# FPGA.net
KiCad netlist of a schematic drawn in Altium Designer
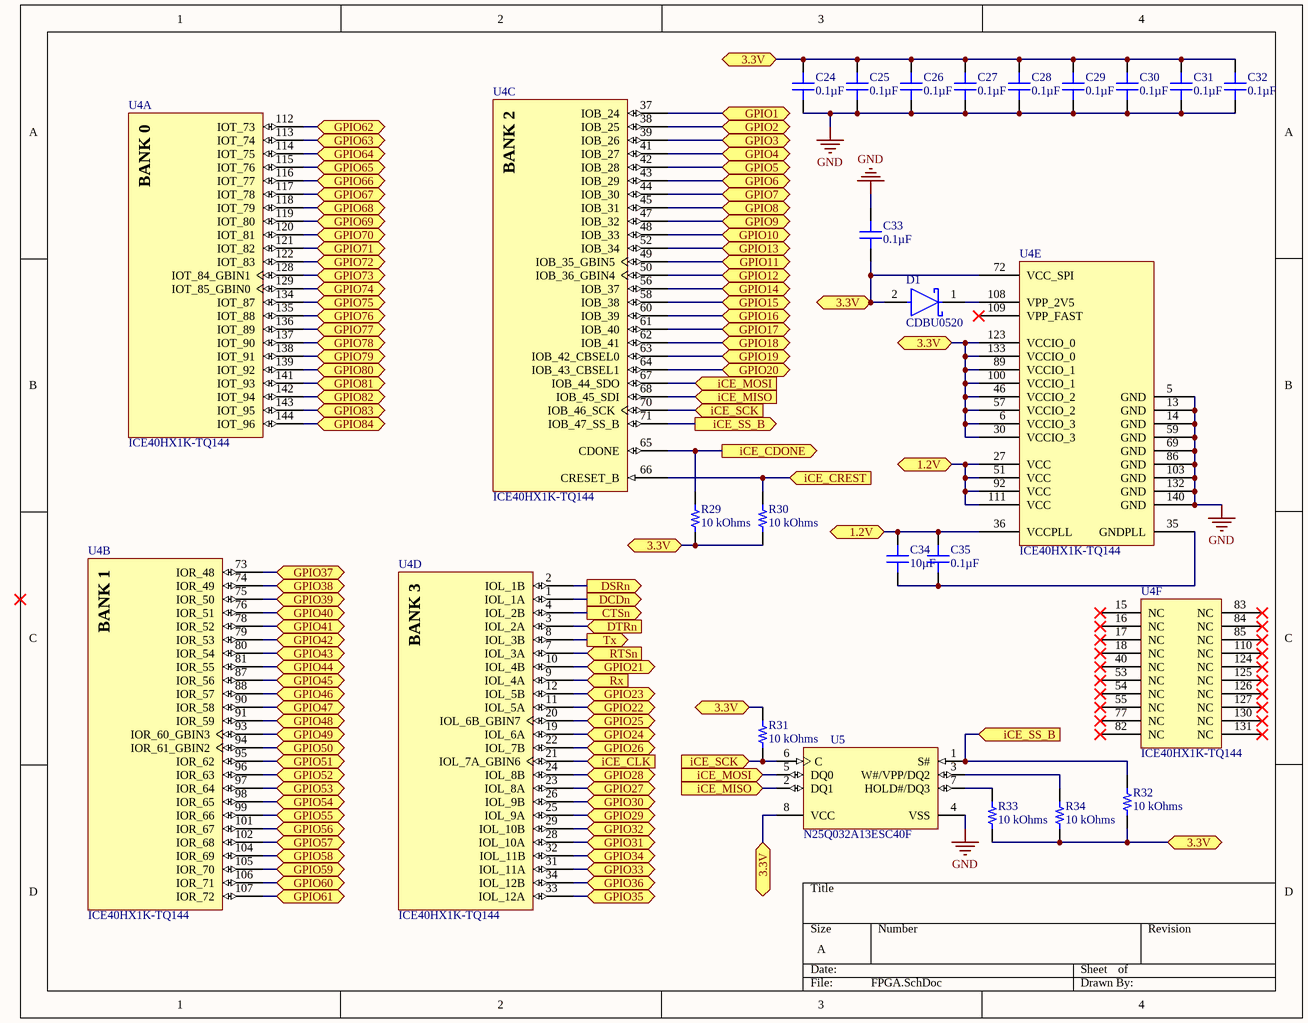
[diagram p0: FPGA.SchDoc]

(export (version "E")
  (design (tool "Eeschema 10.0.6"))
  (components
    (comp (ref "C24")
      (value "0.1µF")
      (footprint "CAP 0805_2012")
      (description "CAP CER 0.1UF 50V X7R 0805")
      (fields
        (field (name "PART NUMBER") "CL21B104KBCNNNC")
        (field (name "MANUFACTURER") "Samsung Electro-Mechanics")
      )
      (libsource (lib "Celestial Altium Library - altium_library") (part "Capacitor"))
    )
    (comp (ref "C25")
      (value "0.1µF")
      (footprint "CAP 0805_2012")
      (description "CAP CER 0.1UF 50V X7R 0805")
      (fields
        (field (name "PART NUMBER") "CL21B104KBCNNNC")
        (field (name "MANUFACTURER") "Samsung Electro-Mechanics")
      )
      (libsource (lib "Celestial Altium Library - altium_library") (part "Capacitor"))
    )
    (comp (ref "C26")
      (value "0.1µF")
      (footprint "CAP 0805_2012")
      (description "CAP CER 0.1UF 50V X7R 0805")
      (fields
        (field (name "PART NUMBER") "CL21B104KBCNNNC")
        (field (name "MANUFACTURER") "Samsung Electro-Mechanics")
      )
      (libsource (lib "Celestial Altium Library - altium_library") (part "Capacitor"))
    )
    (comp (ref "C27")
      (value "0.1µF")
      (footprint "CAP 0805_2012")
      (description "CAP CER 0.1UF 50V X7R 0805")
      (fields
        (field (name "PART NUMBER") "CL21B104KBCNNNC")
        (field (name "MANUFACTURER") "Samsung Electro-Mechanics")
      )
      (libsource (lib "Celestial Altium Library - altium_library") (part "Capacitor"))
    )
    (comp (ref "C28")
      (value "0.1µF")
      (footprint "CAP 0805_2012")
      (description "CAP CER 0.1UF 50V X7R 0805")
      (fields
        (field (name "PART NUMBER") "CL21B104KBCNNNC")
        (field (name "MANUFACTURER") "Samsung Electro-Mechanics")
      )
      (libsource (lib "Celestial Altium Library - altium_library") (part "Capacitor"))
    )
    (comp (ref "C29")
      (value "0.1µF")
      (footprint "CAP 0805_2012")
      (description "CAP CER 0.1UF 50V X7R 0805")
      (fields
        (field (name "PART NUMBER") "CL21B104KBCNNNC")
        (field (name "MANUFACTURER") "Samsung Electro-Mechanics")
      )
      (libsource (lib "Celestial Altium Library - altium_library") (part "Capacitor"))
    )
    (comp (ref "C30")
      (value "0.1µF")
      (footprint "CAP 0805_2012")
      (description "CAP CER 0.1UF 50V X7R 0805")
      (fields
        (field (name "PART NUMBER") "CL21B104KBCNNNC")
        (field (name "MANUFACTURER") "Samsung Electro-Mechanics")
      )
      (libsource (lib "Celestial Altium Library - altium_library") (part "Capacitor"))
    )
    (comp (ref "C31")
      (value "0.1µF")
      (footprint "CAP 0805_2012")
      (description "CAP CER 0.1UF 50V X7R 0805")
      (fields
        (field (name "PART NUMBER") "CL21B104KBCNNNC")
        (field (name "MANUFACTURER") "Samsung Electro-Mechanics")
      )
      (libsource (lib "Celestial Altium Library - altium_library") (part "Capacitor"))
    )
    (comp (ref "C32")
      (value "0.1µF")
      (footprint "CAP 0805_2012")
      (description "CAP CER 0.1UF 50V X7R 0805")
      (fields
        (field (name "PART NUMBER") "CL21B104KBCNNNC")
        (field (name "MANUFACTURER") "Samsung Electro-Mechanics")
      )
      (libsource (lib "Celestial Altium Library - altium_library") (part "Capacitor"))
    )
    (comp (ref "C33")
      (value "0.1µF")
      (footprint "CAP 0805_2012")
      (description "CAP CER 0.1UF 50V X7R 0805")
      (fields
        (field (name "PART NUMBER") "CL21B104KBCNNNC")
        (field (name "MANUFACTURER") "Samsung Electro-Mechanics")
      )
      (libsource (lib "Celestial Altium Library - altium_library") (part "Capacitor"))
    )
    (comp (ref "C34")
      (value "10µF")
      (footprint "CAP 0805_2012")
      (description "CAP CER 10UF 16V X5R 0805")
      (fields
        (field (name "PART NUMBER") "CL21A106KOQNNNG")
        (field (name "MANUFACTURER") "Samsung Electro-Mechanics")
      )
      (libsource (lib "Celestial Altium Library - altium_library") (part "Capacitor"))
    )
    (comp (ref "C35")
      (value "0.1µF")
      (footprint "CAP 0805_2012")
      (description "CAP CER 0.1UF 50V X7R 0805")
      (fields
        (field (name "PART NUMBER") "CL21B104KBCNNNC")
        (field (name "MANUFACTURER") "Samsung Electro-Mechanics")
      )
      (libsource (lib "Celestial Altium Library - altium_library") (part "Capacitor"))
    )
    (comp (ref "D1")
      (value "CDBU0520")
      (footprint "FP-0603-SOD-523F-MFG")
      (description "DIODE SCHOTTKY 20V 500MA 0603")
      (libsource (lib "Altium Content Vault") (part "1d6ec82d83fb6aee721767c19dac4b9"))
    )
    (comp (ref "R29")
      (value "10 kOhms")
      (footprint "RES 0805_2012")
      (description "RES 10K OHM 1% 1/4W 0805")
      (fields
        (field (name "PART NUMBER") "RNCP0805FTD10K0")
        (field (name "MANUFACTURER") "Stackpole Electronics Inc")
      )
      (libsource (lib "Celestial Altium Library - altium_library") (part "Resistor"))
    )
    (comp (ref "R30")
      (value "10 kOhms")
      (footprint "RES 0805_2012")
      (description "RES 10K OHM 1% 1/4W 0805")
      (fields
        (field (name "PART NUMBER") "RNCP0805FTD10K0")
        (field (name "MANUFACTURER") "Stackpole Electronics Inc")
      )
      (libsource (lib "Celestial Altium Library - altium_library") (part "Resistor"))
    )
    (comp (ref "R31")
      (value "10 kOhms")
      (footprint "RES 0805_2012")
      (description "RES 10K OHM 1% 1/4W 0805")
      (fields
        (field (name "PART NUMBER") "RNCP0805FTD10K0")
        (field (name "MANUFACTURER") "Stackpole Electronics Inc")
      )
      (libsource (lib "Celestial Altium Library - altium_library") (part "Resistor"))
    )
    (comp (ref "R32")
      (value "10 kOhms")
      (footprint "RES 0805_2012")
      (description "RES 10K OHM 1% 1/4W 0805")
      (fields
        (field (name "PART NUMBER") "RNCP0805FTD10K0")
        (field (name "MANUFACTURER") "Stackpole Electronics Inc")
      )
      (libsource (lib "Celestial Altium Library - altium_library") (part "Resistor"))
    )
    (comp (ref "R33")
      (value "10 kOhms")
      (footprint "RES 0805_2012")
      (description "RES 10K OHM 1% 1/4W 0805")
      (fields
        (field (name "PART NUMBER") "RNCP0805FTD10K0")
        (field (name "MANUFACTURER") "Stackpole Electronics Inc")
      )
      (libsource (lib "Celestial Altium Library - altium_library") (part "Resistor"))
    )
    (comp (ref "R34")
      (value "10 kOhms")
      (footprint "RES 0805_2012")
      (description "RES 10K OHM 1% 1/4W 0805")
      (fields
        (field (name "PART NUMBER") "RNCP0805FTD10K0")
        (field (name "MANUFACTURER") "Stackpole Electronics Inc")
      )
      (libsource (lib "Celestial Altium Library - altium_library") (part "Resistor"))
    )
    (comp (ref "U4")
      (value "ICE40HX1K-TQ144")
      (footprint "LATC-TQFP-144_L")
      (fields (field (name "MANUFACTURER") "Lattice Semiconductor"))
      (libsource (lib "Altium Content Vault") (part "LATC-HX1K-TQFP-144"))
    )
    (comp (ref "U5")
      (value "N25Q032A13ESC40F")
      (footprint "MICT-SC-8_N")
      (fields (field (name "MANUFACTURER") "Micron") (field (name "VOLTAGE") "2.7V-3.6VÂ "))
      (libsource (lib "Altium Content Vault") (part "MICT-N25Q032SC-8"))
    )
  )
  (nets
    (net (code "1") (name "/1.2V") (class "Default")
      (node (ref "C34") (pin "2") (pinfunction "2_2") (pintype "passive"))
      (node (ref "C35") (pin "2") (pinfunction "2_2") (pintype "passive"))
      (node (ref "U4") (pin "111") (pinfunction "VCC_111") (pintype "power_in"))
      (node (ref "U4") (pin "27") (pinfunction "VCC_27") (pintype "power_in"))
      (node (ref "U4") (pin "36") (pinfunction "VCCPLL_36") (pintype "power_in"))
      (node (ref "U4") (pin "51") (pinfunction "VCC_51") (pintype "power_in"))
      (node (ref "U4") (pin "92") (pinfunction "VCC_92") (pintype "power_in"))
    )
    (net (code "2") (name "/3.3V") (class "Default")
      (node (ref "C24") (pin "2") (pinfunction "2_2") (pintype "passive"))
      (node (ref "C25") (pin "2") (pinfunction "2_2") (pintype "passive"))
      (node (ref "C26") (pin "2") (pinfunction "2_2") (pintype "passive"))
      (node (ref "C27") (pin "2") (pinfunction "2_2") (pintype "passive"))
      (node (ref "C28") (pin "2") (pinfunction "2_2") (pintype "passive"))
      (node (ref "C29") (pin "2") (pinfunction "2_2") (pintype "passive"))
      (node (ref "C30") (pin "2") (pinfunction "2_2") (pintype "passive"))
      (node (ref "C31") (pin "2") (pinfunction "2_2") (pintype "passive"))
      (node (ref "C32") (pin "2") (pinfunction "2_2") (pintype "passive"))
      (node (ref "C33") (pin "1") (pinfunction "1_1") (pintype "passive"))
      (node (ref "D1") (pin "2") (pinfunction "A_2") (pintype "passive"))
      (node (ref "R29") (pin "2") (pinfunction "2_2") (pintype "passive"))
      (node (ref "R30") (pin "2") (pinfunction "2_2") (pintype "passive"))
      (node (ref "R31") (pin "2") (pinfunction "2_2") (pintype "passive"))
      (node (ref "R32") (pin "1") (pinfunction "1_1") (pintype "passive"))
      (node (ref "R33") (pin "1") (pinfunction "1_1") (pintype "passive"))
      (node (ref "R34") (pin "1") (pinfunction "1_1") (pintype "passive"))
      (node (ref "U4") (pin "100") (pinfunction "VCCIO_1_100") (pintype "power_in"))
      (node (ref "U4") (pin "123") (pinfunction "VCCIO_0_123") (pintype "power_in"))
      (node (ref "U4") (pin "133") (pinfunction "VCCIO_0_133") (pintype "power_in"))
      (node (ref "U4") (pin "30") (pinfunction "VCCIO_3_30") (pintype "power_in"))
      (node (ref "U4") (pin "46") (pinfunction "VCCIO_2_46") (pintype "power_in"))
      (node (ref "U4") (pin "57") (pinfunction "VCCIO_2_57") (pintype "power_in"))
      (node (ref "U4") (pin "6") (pinfunction "VCCIO_3_6") (pintype "power_in"))
      (node (ref "U4") (pin "72") (pinfunction "VCC_SPI_72") (pintype "power_in"))
      (node (ref "U4") (pin "89") (pinfunction "VCCIO_1_89") (pintype "power_in"))
      (node (ref "U5") (pin "8") (pinfunction "VCC_8") (pintype "power_in"))
    )
    (net (code "3") (name "/CTSn") (class "Default")
      (node (ref "U4") (pin "4") (pinfunction "IOL_2B_4") (pintype "bidirectional"))
    )
    (net (code "4") (name "/DCDn") (class "Default")
      (node (ref "U4") (pin "1") (pinfunction "IOL_1A_1") (pintype "bidirectional"))
    )
    (net (code "5") (name "/DSRn") (class "Default")
      (node (ref "U4") (pin "2") (pinfunction "IOL_1B_2") (pintype "bidirectional"))
    )
    (net (code "6") (name "/DTRn") (class "Default")
      (node (ref "U4") (pin "3") (pinfunction "IOL_2A_3") (pintype "bidirectional"))
    )
    (net (code "7") (name "/GPIO1") (class "Default")
      (node (ref "U4") (pin "37") (pinfunction "IOB_24_37") (pintype "bidirectional"))
    )
    (net (code "8") (name "/GPIO2") (class "Default")
      (node (ref "U4") (pin "38") (pinfunction "IOB_25_38") (pintype "bidirectional"))
    )
    (net (code "9") (name "/GPIO3") (class "Default")
      (node (ref "U4") (pin "39") (pinfunction "IOB_26_39") (pintype "bidirectional"))
    )
    (net (code "10") (name "/GPIO4") (class "Default")
      (node (ref "U4") (pin "41") (pinfunction "IOB_27_41") (pintype "bidirectional"))
    )
    (net (code "11") (name "/GPIO5") (class "Default")
      (node (ref "U4") (pin "42") (pinfunction "IOB_28_42") (pintype "bidirectional"))
    )
    (net (code "12") (name "/GPIO6") (class "Default")
      (node (ref "U4") (pin "43") (pinfunction "IOB_29_43") (pintype "bidirectional"))
    )
    (net (code "13") (name "/GPIO7") (class "Default")
      (node (ref "U4") (pin "44") (pinfunction "IOB_30_44") (pintype "bidirectional"))
    )
    (net (code "14") (name "/GPIO8") (class "Default")
      (node (ref "U4") (pin "45") (pinfunction "IOB_31_45") (pintype "bidirectional"))
    )
    (net (code "15") (name "/GPIO9") (class "Default")
      (node (ref "U4") (pin "47") (pinfunction "IOB_32_47") (pintype "bidirectional"))
    )
    (net (code "16") (name "/GPIO10") (class "Default")
      (node (ref "U4") (pin "48") (pinfunction "IOB_33_48") (pintype "bidirectional"))
    )
    (net (code "17") (name "/GPIO11") (class "Default")
      (node (ref "U4") (pin "49") (pinfunction "IOB_35_GBIN5_49") (pintype "bidirectional"))
    )
    (net (code "18") (name "/GPIO12") (class "Default")
      (node (ref "U4") (pin "50") (pinfunction "IOB_36_GBIN4_50") (pintype "bidirectional"))
    )
    (net (code "19") (name "/GPIO13") (class "Default")
      (node (ref "U4") (pin "52") (pinfunction "IOB_34_52") (pintype "bidirectional"))
    )
    (net (code "20") (name "/GPIO14") (class "Default")
      (node (ref "U4") (pin "56") (pinfunction "IOB_37_56") (pintype "bidirectional"))
    )
    (net (code "21") (name "/GPIO15") (class "Default")
      (node (ref "U4") (pin "58") (pinfunction "IOB_38_58") (pintype "bidirectional"))
    )
    (net (code "22") (name "/GPIO16") (class "Default")
      (node (ref "U4") (pin "60") (pinfunction "IOB_39_60") (pintype "bidirectional"))
    )
    (net (code "23") (name "/GPIO17") (class "Default")
      (node (ref "U4") (pin "61") (pinfunction "IOB_40_61") (pintype "bidirectional"))
    )
    (net (code "24") (name "/GPIO18") (class "Default")
      (node (ref "U4") (pin "62") (pinfunction "IOB_41_62") (pintype "bidirectional"))
    )
    (net (code "25") (name "/GPIO19") (class "Default")
      (node (ref "U4") (pin "63") (pinfunction "IOB_42_CBSEL0_63") (pintype "bidirectional"))
    )
    (net (code "26") (name "/GPIO20") (class "Default")
      (node (ref "U4") (pin "64") (pinfunction "IOB_43_CBSEL1_64") (pintype "bidirectional"))
    )
    (net (code "27") (name "/GPIO21") (class "Default")
      (node (ref "U4") (pin "10") (pinfunction "IOL_4B_10") (pintype "bidirectional"))
    )
    (net (code "28") (name "/GPIO22") (class "Default")
      (node (ref "U4") (pin "11") (pinfunction "IOL_5A_11") (pintype "bidirectional"))
    )
    (net (code "29") (name "/GPIO23") (class "Default")
      (node (ref "U4") (pin "12") (pinfunction "IOL_5B_12") (pintype "bidirectional"))
    )
    (net (code "30") (name "/GPIO24") (class "Default")
      (node (ref "U4") (pin "19") (pinfunction "IOL_6A_19") (pintype "bidirectional"))
    )
    (net (code "31") (name "/GPIO25") (class "Default")
      (node (ref "U4") (pin "20") (pinfunction "IOL_6B_GBIN7_20") (pintype "bidirectional"))
    )
    (net (code "32") (name "/GPIO26") (class "Default")
      (node (ref "U4") (pin "22") (pinfunction "IOL_7B_22") (pintype "bidirectional"))
    )
    (net (code "33") (name "/GPIO27") (class "Default")
      (node (ref "U4") (pin "23") (pinfunction "IOL_8A_23") (pintype "bidirectional"))
    )
    (net (code "34") (name "/GPIO28") (class "Default")
      (node (ref "U4") (pin "24") (pinfunction "IOL_8B_24") (pintype "bidirectional"))
    )
    (net (code "35") (name "/GPIO29") (class "Default")
      (node (ref "U4") (pin "25") (pinfunction "IOL_9A_25") (pintype "bidirectional"))
    )
    (net (code "36") (name "/GPIO30") (class "Default")
      (node (ref "U4") (pin "26") (pinfunction "IOL_9B_26") (pintype "bidirectional"))
    )
    (net (code "37") (name "/GPIO31") (class "Default")
      (node (ref "U4") (pin "28") (pinfunction "IOL_10A_28") (pintype "bidirectional"))
    )
    (net (code "38") (name "/GPIO32") (class "Default")
      (node (ref "U4") (pin "29") (pinfunction "IOL_10B_29") (pintype "bidirectional"))
    )
    (net (code "39") (name "/GPIO33") (class "Default")
      (node (ref "U4") (pin "31") (pinfunction "IOL_11A_31") (pintype "bidirectional"))
    )
    (net (code "40") (name "/GPIO34") (class "Default")
      (node (ref "U4") (pin "32") (pinfunction "IOL_11B_32") (pintype "bidirectional"))
    )
    (net (code "41") (name "/GPIO35") (class "Default")
      (node (ref "U4") (pin "33") (pinfunction "IOL_12A_33") (pintype "bidirectional"))
    )
    (net (code "42") (name "/GPIO36") (class "Default")
      (node (ref "U4") (pin "34") (pinfunction "IOL_12B_34") (pintype "bidirectional"))
    )
    (net (code "43") (name "/GPIO37") (class "Default")
      (node (ref "U4") (pin "73") (pinfunction "IOR_48_73") (pintype "bidirectional"))
    )
    (net (code "44") (name "/GPIO38") (class "Default")
      (node (ref "U4") (pin "74") (pinfunction "IOR_49_74") (pintype "bidirectional"))
    )
    (net (code "45") (name "/GPIO39") (class "Default")
      (node (ref "U4") (pin "75") (pinfunction "IOR_50_75") (pintype "bidirectional"))
    )
    (net (code "46") (name "/GPIO40") (class "Default")
      (node (ref "U4") (pin "76") (pinfunction "IOR_51_76") (pintype "bidirectional"))
    )
    (net (code "47") (name "/GPIO41") (class "Default")
      (node (ref "U4") (pin "78") (pinfunction "IOR_52_78") (pintype "bidirectional"))
    )
    (net (code "48") (name "/GPIO42") (class "Default")
      (node (ref "U4") (pin "79") (pinfunction "IOR_53_79") (pintype "bidirectional"))
    )
    (net (code "49") (name "/GPIO43") (class "Default")
      (node (ref "U4") (pin "80") (pinfunction "IOR_54_80") (pintype "bidirectional"))
    )
    (net (code "50") (name "/GPIO44") (class "Default")
      (node (ref "U4") (pin "81") (pinfunction "IOR_55_81") (pintype "bidirectional"))
    )
    (net (code "51") (name "/GPIO45") (class "Default")
      (node (ref "U4") (pin "87") (pinfunction "IOR_56_87") (pintype "bidirectional"))
    )
    (net (code "52") (name "/GPIO46") (class "Default")
      (node (ref "U4") (pin "88") (pinfunction "IOR_57_88") (pintype "bidirectional"))
    )
    (net (code "53") (name "/GPIO47") (class "Default")
      (node (ref "U4") (pin "90") (pinfunction "IOR_58_90") (pintype "bidirectional"))
    )
    (net (code "54") (name "/GPIO48") (class "Default")
      (node (ref "U4") (pin "91") (pinfunction "IOR_59_91") (pintype "bidirectional"))
    )
    (net (code "55") (name "/GPIO49") (class "Default")
      (node (ref "U4") (pin "93") (pinfunction "IOR_60_GBIN3_93") (pintype "bidirectional"))
    )
    (net (code "56") (name "/GPIO50") (class "Default")
      (node (ref "U4") (pin "94") (pinfunction "IOR_61_GBIN2_94") (pintype "bidirectional"))
    )
    (net (code "57") (name "/GPIO51") (class "Default")
      (node (ref "U4") (pin "95") (pinfunction "IOR_62_95") (pintype "bidirectional"))
    )
    (net (code "58") (name "/GPIO52") (class "Default")
      (node (ref "U4") (pin "96") (pinfunction "IOR_63_96") (pintype "bidirectional"))
    )
    (net (code "59") (name "/GPIO53") (class "Default")
      (node (ref "U4") (pin "97") (pinfunction "IOR_64_97") (pintype "bidirectional"))
    )
    (net (code "60") (name "/GPIO54") (class "Default")
      (node (ref "U4") (pin "98") (pinfunction "IOR_65_98") (pintype "bidirectional"))
    )
    (net (code "61") (name "/GPIO55") (class "Default")
      (node (ref "U4") (pin "99") (pinfunction "IOR_66_99") (pintype "bidirectional"))
    )
    (net (code "62") (name "/GPIO56") (class "Default")
      (node (ref "U4") (pin "101") (pinfunction "IOR_67_101") (pintype "bidirectional"))
    )
    (net (code "63") (name "/GPIO57") (class "Default")
      (node (ref "U4") (pin "102") (pinfunction "IOR_68_102") (pintype "bidirectional"))
    )
    (net (code "64") (name "/GPIO58") (class "Default")
      (node (ref "U4") (pin "104") (pinfunction "IOR_69_104") (pintype "bidirectional"))
    )
    (net (code "65") (name "/GPIO59") (class "Default")
      (node (ref "U4") (pin "105") (pinfunction "IOR_70_105") (pintype "bidirectional"))
    )
    (net (code "66") (name "/GPIO60") (class "Default")
      (node (ref "U4") (pin "106") (pinfunction "IOR_71_106") (pintype "bidirectional"))
    )
    (net (code "67") (name "/GPIO61") (class "Default")
      (node (ref "U4") (pin "107") (pinfunction "IOR_72_107") (pintype "bidirectional"))
    )
    (net (code "68") (name "/GPIO62") (class "Default")
      (node (ref "U4") (pin "112") (pinfunction "IOT_73_112") (pintype "bidirectional"))
    )
    (net (code "69") (name "/GPIO63") (class "Default")
      (node (ref "U4") (pin "113") (pinfunction "IOT_74_113") (pintype "bidirectional"))
    )
    (net (code "70") (name "/GPIO64") (class "Default")
      (node (ref "U4") (pin "114") (pinfunction "IOT_75_114") (pintype "bidirectional"))
    )
    (net (code "71") (name "/GPIO65") (class "Default")
      (node (ref "U4") (pin "115") (pinfunction "IOT_76_115") (pintype "bidirectional"))
    )
    (net (code "72") (name "/GPIO66") (class "Default")
      (node (ref "U4") (pin "116") (pinfunction "IOT_77_116") (pintype "bidirectional"))
    )
    (net (code "73") (name "/GPIO67") (class "Default")
      (node (ref "U4") (pin "117") (pinfunction "IOT_78_117") (pintype "bidirectional"))
    )
    (net (code "74") (name "/GPIO68") (class "Default")
      (node (ref "U4") (pin "118") (pinfunction "IOT_79_118") (pintype "bidirectional"))
    )
    (net (code "75") (name "/GPIO69") (class "Default")
      (node (ref "U4") (pin "119") (pinfunction "IOT_80_119") (pintype "bidirectional"))
    )
    (net (code "76") (name "/GPIO70") (class "Default")
      (node (ref "U4") (pin "120") (pinfunction "IOT_81_120") (pintype "bidirectional"))
    )
    (net (code "77") (name "/GPIO71") (class "Default")
      (node (ref "U4") (pin "121") (pinfunction "IOT_82_121") (pintype "bidirectional"))
    )
    (net (code "78") (name "/GPIO72") (class "Default")
      (node (ref "U4") (pin "122") (pinfunction "IOT_83_122") (pintype "bidirectional"))
    )
    (net (code "79") (name "/GPIO73") (class "Default")
      (node (ref "U4") (pin "128") (pinfunction "IOT_84_GBIN1_128") (pintype "bidirectional"))
    )
    (net (code "80") (name "/GPIO74") (class "Default")
      (node (ref "U4") (pin "129") (pinfunction "IOT_85_GBIN0_129") (pintype "bidirectional"))
    )
    (net (code "81") (name "/GPIO75") (class "Default")
      (node (ref "U4") (pin "134") (pinfunction "IOT_87_134") (pintype "bidirectional"))
    )
    (net (code "82") (name "/GPIO76") (class "Default")
      (node (ref "U4") (pin "135") (pinfunction "IOT_88_135") (pintype "bidirectional"))
    )
    (net (code "83") (name "/GPIO77") (class "Default")
      (node (ref "U4") (pin "136") (pinfunction "IOT_89_136") (pintype "bidirectional"))
    )
    (net (code "84") (name "/GPIO78") (class "Default")
      (node (ref "U4") (pin "137") (pinfunction "IOT_90_137") (pintype "bidirectional"))
    )
    (net (code "85") (name "/GPIO79") (class "Default")
      (node (ref "U4") (pin "138") (pinfunction "IOT_91_138") (pintype "bidirectional"))
    )
    (net (code "86") (name "/GPIO80") (class "Default")
      (node (ref "U4") (pin "139") (pinfunction "IOT_92_139") (pintype "bidirectional"))
    )
    (net (code "87") (name "/GPIO81") (class "Default")
      (node (ref "U4") (pin "141") (pinfunction "IOT_93_141") (pintype "bidirectional"))
    )
    (net (code "88") (name "/GPIO82") (class "Default")
      (node (ref "U4") (pin "142") (pinfunction "IOT_94_142") (pintype "bidirectional"))
    )
    (net (code "89") (name "/GPIO83") (class "Default")
      (node (ref "U4") (pin "143") (pinfunction "IOT_95_143") (pintype "bidirectional"))
    )
    (net (code "90") (name "/GPIO84") (class "Default")
      (node (ref "U4") (pin "144") (pinfunction "IOT_96_144") (pintype "bidirectional"))
    )
    (net (code "91") (name "/RTSn") (class "Default")
      (node (ref "U4") (pin "7") (pinfunction "IOL_3A_7") (pintype "bidirectional"))
    )
    (net (code "92") (name "/Rx") (class "Default")
      (node (ref "U4") (pin "9") (pinfunction "IOL_4A_9") (pintype "bidirectional"))
    )
    (net (code "93") (name "/Tx") (class "Default")
      (node (ref "U4") (pin "8") (pinfunction "IOL_3B_8") (pintype "bidirectional"))
    )
    (net (code "94") (name "/iCE_CDONE") (class "Default")
      (node (ref "R29") (pin "1") (pinfunction "1_1") (pintype "passive"))
      (node (ref "U4") (pin "65") (pinfunction "CDONE_65") (pintype "bidirectional"))
    )
    (net (code "95") (name "/iCE_CLK") (class "Default")
      (node (ref "U4") (pin "21") (pinfunction "IOL_7A_GBIN6_21") (pintype "bidirectional"))
    )
    (net (code "96") (name "/iCE_CREST") (class "Default")
      (node (ref "R30") (pin "1") (pinfunction "1_1") (pintype "passive"))
      (node (ref "U4") (pin "66") (pinfunction "CRESET_B_66") (pintype "input"))
    )
    (net (code "97") (name "/iCE_MISO") (class "Default")
      (node (ref "U4") (pin "68") (pinfunction "IOB_45_SDI_68") (pintype "bidirectional"))
      (node (ref "U5") (pin "2") (pinfunction "DQ1_2") (pintype "bidirectional"))
    )
    (net (code "98") (name "/iCE_MOSI") (class "Default")
      (node (ref "U4") (pin "67") (pinfunction "IOB_44_SDO_67") (pintype "bidirectional"))
      (node (ref "U5") (pin "5") (pinfunction "DQ0_5") (pintype "bidirectional"))
    )
    (net (code "99") (name "/iCE_SCK") (class "Default")
      (node (ref "R31") (pin "1") (pinfunction "1_1") (pintype "passive"))
      (node (ref "U4") (pin "70") (pinfunction "IOB_46_SCK_70") (pintype "bidirectional"))
      (node (ref "U5") (pin "6") (pinfunction "C_6") (pintype "input"))
    )
    (net (code "100") (name "/iCE_SS_B") (class "Default")
      (node (ref "R32") (pin "2") (pinfunction "2_2") (pintype "passive"))
      (node (ref "U4") (pin "71") (pinfunction "IOB_47_SS_B_71") (pintype "bidirectional"))
      (node (ref "U5") (pin "1") (pinfunction "S#_1") (pintype "input"))
    )
    (net (code "101") (name "GND") (class "Default")
      (node (ref "C24") (pin "1") (pinfunction "1_1") (pintype "passive"))
      (node (ref "C25") (pin "1") (pinfunction "1_1") (pintype "passive"))
      (node (ref "C26") (pin "1") (pinfunction "1_1") (pintype "passive"))
      (node (ref "C27") (pin "1") (pinfunction "1_1") (pintype "passive"))
      (node (ref "C28") (pin "1") (pinfunction "1_1") (pintype "passive"))
      (node (ref "C29") (pin "1") (pinfunction "1_1") (pintype "passive"))
      (node (ref "C30") (pin "1") (pinfunction "1_1") (pintype "passive"))
      (node (ref "C31") (pin "1") (pinfunction "1_1") (pintype "passive"))
      (node (ref "C32") (pin "1") (pinfunction "1_1") (pintype "passive"))
      (node (ref "C33") (pin "2") (pinfunction "2_2") (pintype "passive"))
      (node (ref "U4") (pin "103") (pinfunction "GND_103") (pintype "power_in"))
      (node (ref "U4") (pin "13") (pinfunction "GND_13") (pintype "power_in"))
      (node (ref "U4") (pin "132") (pinfunction "GND_132") (pintype "power_in"))
      (node (ref "U4") (pin "14") (pinfunction "GND_14") (pintype "power_in"))
      (node (ref "U4") (pin "140") (pinfunction "GND_140") (pintype "power_in"))
      (node (ref "U4") (pin "5") (pinfunction "GND_5") (pintype "power_in"))
      (node (ref "U4") (pin "59") (pinfunction "GND_59") (pintype "power_in"))
      (node (ref "U4") (pin "69") (pinfunction "GND_69") (pintype "power_in"))
      (node (ref "U4") (pin "86") (pinfunction "GND_86") (pintype "power_in"))
      (node (ref "U5") (pin "4") (pinfunction "VSS_4") (pintype "power_in"))
    )
    (net (code "102") (name "Net-(D1-C)") (class "Default")
      (node (ref "D1") (pin "1") (pinfunction "C_1") (pintype "passive"))
      (node (ref "U4") (pin "108") (pinfunction "VPP_2V5_108") (pintype "power_in"))
    )
    (net (code "103") (name "Net-(U4E-GNDPLL)") (class "Default")
      (node (ref "C34") (pin "1") (pinfunction "1_1") (pintype "passive"))
      (node (ref "C35") (pin "1") (pinfunction "1_1") (pintype "passive"))
      (node (ref "U4") (pin "35") (pinfunction "GNDPLL_35") (pintype "power_in"))
    )
    (net (code "104") (name "Net-(U5-HOLD#{slash}DQ3)") (class "Default")
      (node (ref "R33") (pin "2") (pinfunction "2_2") (pintype "passive"))
      (node (ref "U5") (pin "7") (pinfunction "HOLD#/DQ3_7") (pintype "bidirectional"))
    )
    (net (code "105") (name "Net-(U5-W#{slash}VPP{slash}DQ2)") (class "Default")
      (node (ref "R34") (pin "2") (pinfunction "2_2") (pintype "passive"))
      (node (ref "U5") (pin "3") (pinfunction "W#/VPP/DQ2_3") (pintype "bidirectional"))
    )
    (net (code "106") (name "unconnected-(U4E-VPP_FAST-Pad109)") (class "Default")
      (node (ref "U4") (pin "109") (pinfunction "VPP_FAST_109") (pintype "power_in+no_connect"))
    )
    (net (code "107") (name "unconnected-(U4F-NC-Pad15)") (class "Default")
      (node (ref "U4") (pin "15") (pinfunction "NC_15") (pintype "passive+no_connect"))
    )
    (net (code "108") (name "unconnected-(U4F-NC-Pad16)") (class "Default")
      (node (ref "U4") (pin "16") (pinfunction "NC_16") (pintype "passive+no_connect"))
    )
    (net (code "109") (name "unconnected-(U4F-NC-Pad17)") (class "Default")
      (node (ref "U4") (pin "17") (pinfunction "NC_17") (pintype "passive+no_connect"))
    )
    (net (code "110") (name "unconnected-(U4F-NC-Pad18)") (class "Default")
      (node (ref "U4") (pin "18") (pinfunction "NC_18") (pintype "passive+no_connect"))
    )
    (net (code "111") (name "unconnected-(U4F-NC-Pad40)") (class "Default")
      (node (ref "U4") (pin "40") (pinfunction "NC_40") (pintype "passive+no_connect"))
    )
    (net (code "112") (name "unconnected-(U4F-NC-Pad53)") (class "Default")
      (node (ref "U4") (pin "53") (pinfunction "NC_53") (pintype "passive+no_connect"))
    )
    (net (code "113") (name "unconnected-(U4F-NC-Pad54)") (class "Default")
      (node (ref "U4") (pin "54") (pinfunction "NC_54") (pintype "passive+no_connect"))
    )
    (net (code "114") (name "unconnected-(U4F-NC-Pad55)") (class "Default")
      (node (ref "U4") (pin "55") (pinfunction "NC_55") (pintype "passive+no_connect"))
    )
    (net (code "115") (name "unconnected-(U4F-NC-Pad77)") (class "Default")
      (node (ref "U4") (pin "77") (pinfunction "NC_77") (pintype "passive+no_connect"))
    )
    (net (code "116") (name "unconnected-(U4F-NC-Pad82)") (class "Default")
      (node (ref "U4") (pin "82") (pinfunction "NC_82") (pintype "passive+no_connect"))
    )
    (net (code "117") (name "unconnected-(U4F-NC-Pad83)") (class "Default")
      (node (ref "U4") (pin "83") (pinfunction "NC_83") (pintype "passive+no_connect"))
    )
    (net (code "118") (name "unconnected-(U4F-NC-Pad84)") (class "Default")
      (node (ref "U4") (pin "84") (pinfunction "NC_84") (pintype "passive+no_connect"))
    )
    (net (code "119") (name "unconnected-(U4F-NC-Pad85)") (class "Default")
      (node (ref "U4") (pin "85") (pinfunction "NC_85") (pintype "passive+no_connect"))
    )
    (net (code "120") (name "unconnected-(U4F-NC-Pad110)") (class "Default")
      (node (ref "U4") (pin "110") (pinfunction "NC_110") (pintype "passive+no_connect"))
    )
    (net (code "121") (name "unconnected-(U4F-NC-Pad124)") (class "Default")
      (node (ref "U4") (pin "124") (pinfunction "NC_124") (pintype "passive+no_connect"))
    )
    (net (code "122") (name "unconnected-(U4F-NC-Pad125)") (class "Default")
      (node (ref "U4") (pin "125") (pinfunction "NC_125") (pintype "passive+no_connect"))
    )
    (net (code "123") (name "unconnected-(U4F-NC-Pad126)") (class "Default")
      (node (ref "U4") (pin "126") (pinfunction "NC_126") (pintype "passive+no_connect"))
    )
    (net (code "124") (name "unconnected-(U4F-NC-Pad127)") (class "Default")
      (node (ref "U4") (pin "127") (pinfunction "NC_127") (pintype "passive+no_connect"))
    )
    (net (code "125") (name "unconnected-(U4F-NC-Pad130)") (class "Default")
      (node (ref "U4") (pin "130") (pinfunction "NC_130") (pintype "passive+no_connect"))
    )
    (net (code "126") (name "unconnected-(U4F-NC-Pad131)") (class "Default")
      (node (ref "U4") (pin "131") (pinfunction "NC_131") (pintype "passive+no_connect"))
    )
  )
)
